# 5VAC-DCRegulator.net
KiCad netlist of a schematic drawn in EAGLE
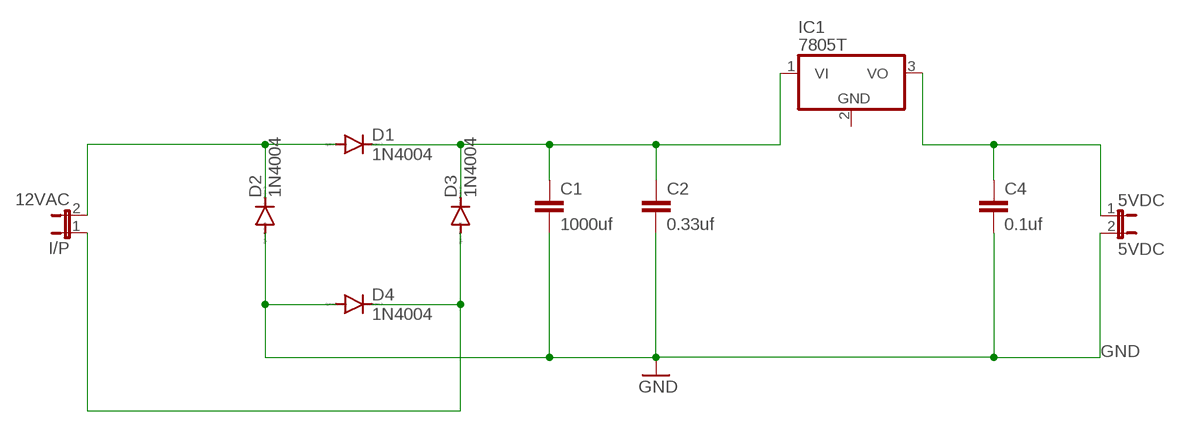
[diagram p0: schematic, sheet 1]

(export (version "E")
  (design (tool "Eeschema 10.0.6"))
  (components
    (comp (ref "5VDC")
      (value "5VDC")
      (footprint "eagle-import:JP1")
      (libsource (lib "eagle-import") (part "JP1E"))
    )
    (comp (ref "C1")
      (value "1000uf")
      (footprint "eagle-import:C2.5-3")
      (libsource (lib "eagle-import") (part "C2,5-3"))
    )
    (comp (ref "C2")
      (value "0.33uf")
      (footprint "eagle-import:C2.5-3")
      (libsource (lib "eagle-import") (part "C2,5-3"))
    )
    (comp (ref "C4")
      (value "0.1uf")
      (footprint "eagle-import:C2.5-3")
      (libsource (lib "eagle-import") (part "C2,5-3"))
    )
    (comp (ref "D1")
      (value "1N4004")
      (footprint "eagle-import:DO41-10")
      (libsource (lib "eagle-import") (part "1N4004"))
    )
    (comp (ref "D2")
      (value "1N4004")
      (footprint "eagle-import:DO41-10")
      (libsource (lib "eagle-import") (part "1N4004"))
    )
    (comp (ref "D3")
      (value "1N4004")
      (footprint "eagle-import:DO41-10")
      (libsource (lib "eagle-import") (part "1N4004"))
    )
    (comp (ref "D4")
      (value "1N4004")
      (footprint "eagle-import:DO41-10")
      (libsource (lib "eagle-import") (part "1N4004"))
    )
    (comp (ref "I/P")
      (value "12VAC")
      (footprint "eagle-import:JP1")
      (libsource (lib "eagle-import") (part "JP1E"))
    )
    (comp (ref "IC1")
      (value "7805T")
      (footprint "eagle-import:TO220H")
      (libsource (lib "eagle-import") (part "78T05"))
    )
  )
  (nets
    (net (code "1") (name "GND") (class "Default")
      (node (ref "5VDC") (pin "2") (pinfunction "2_2") (pintype "passive"))
      (node (ref "C1") (pin "2") (pinfunction "2_2") (pintype "passive"))
      (node (ref "C2") (pin "2") (pinfunction "2_2") (pintype "passive"))
      (node (ref "C4") (pin "2") (pinfunction "2_2") (pintype "passive"))
      (node (ref "D2") (pin "A") (pinfunction "A_A") (pintype "passive"))
      (node (ref "D4") (pin "A") (pinfunction "A_A") (pintype "passive"))
    )
    (net (code "2") (name "Net-(D1-PadA)") (class "Default")
      (node (ref "D1") (pin "A") (pinfunction "A_A") (pintype "passive"))
      (node (ref "D2") (pin "C") (pinfunction "C_C") (pintype "passive"))
      (node (ref "I/P") (pin "2") (pinfunction "2_2") (pintype "passive"))
    )
    (net (code "3") (name "Net-(D3-PadA)") (class "Default")
      (node (ref "D3") (pin "A") (pinfunction "A_A") (pintype "passive"))
      (node (ref "D4") (pin "C") (pinfunction "C_C") (pintype "passive"))
      (node (ref "I/P") (pin "1") (pinfunction "1_1") (pintype "passive"))
    )
    (net (code "4") (name "Net-(IC1-VI)") (class "Default")
      (node (ref "C1") (pin "1") (pinfunction "1_1") (pintype "passive"))
      (node (ref "C2") (pin "1") (pinfunction "1_1") (pintype "passive"))
      (node (ref "D1") (pin "C") (pinfunction "C_C") (pintype "passive"))
      (node (ref "D3") (pin "C") (pinfunction "C_C") (pintype "passive"))
      (node (ref "IC1") (pin "1") (pinfunction "VI_1") (pintype "input"))
    )
    (net (code "5") (name "Net-(IC1-VO)") (class "Default")
      (node (ref "5VDC") (pin "1") (pinfunction "1_1") (pintype "passive"))
      (node (ref "C4") (pin "1") (pinfunction "1_1") (pintype "passive"))
      (node (ref "IC1") (pin "3") (pinfunction "VO_3") (pintype "passive"))
    )
    (net (code "6") (name "unconnected-(IC1-GND-Pad2)") (class "Default")
      (node (ref "IC1") (pin "2") (pinfunction "GND_2") (pintype "passive"))
    )
  )
)
